# PiHat.net
KiCad netlist of a schematic drawn in EAGLE
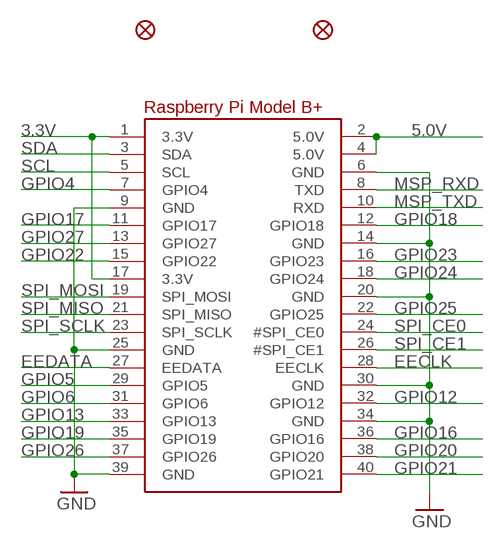
[diagram p0: schematic, sheet 1]
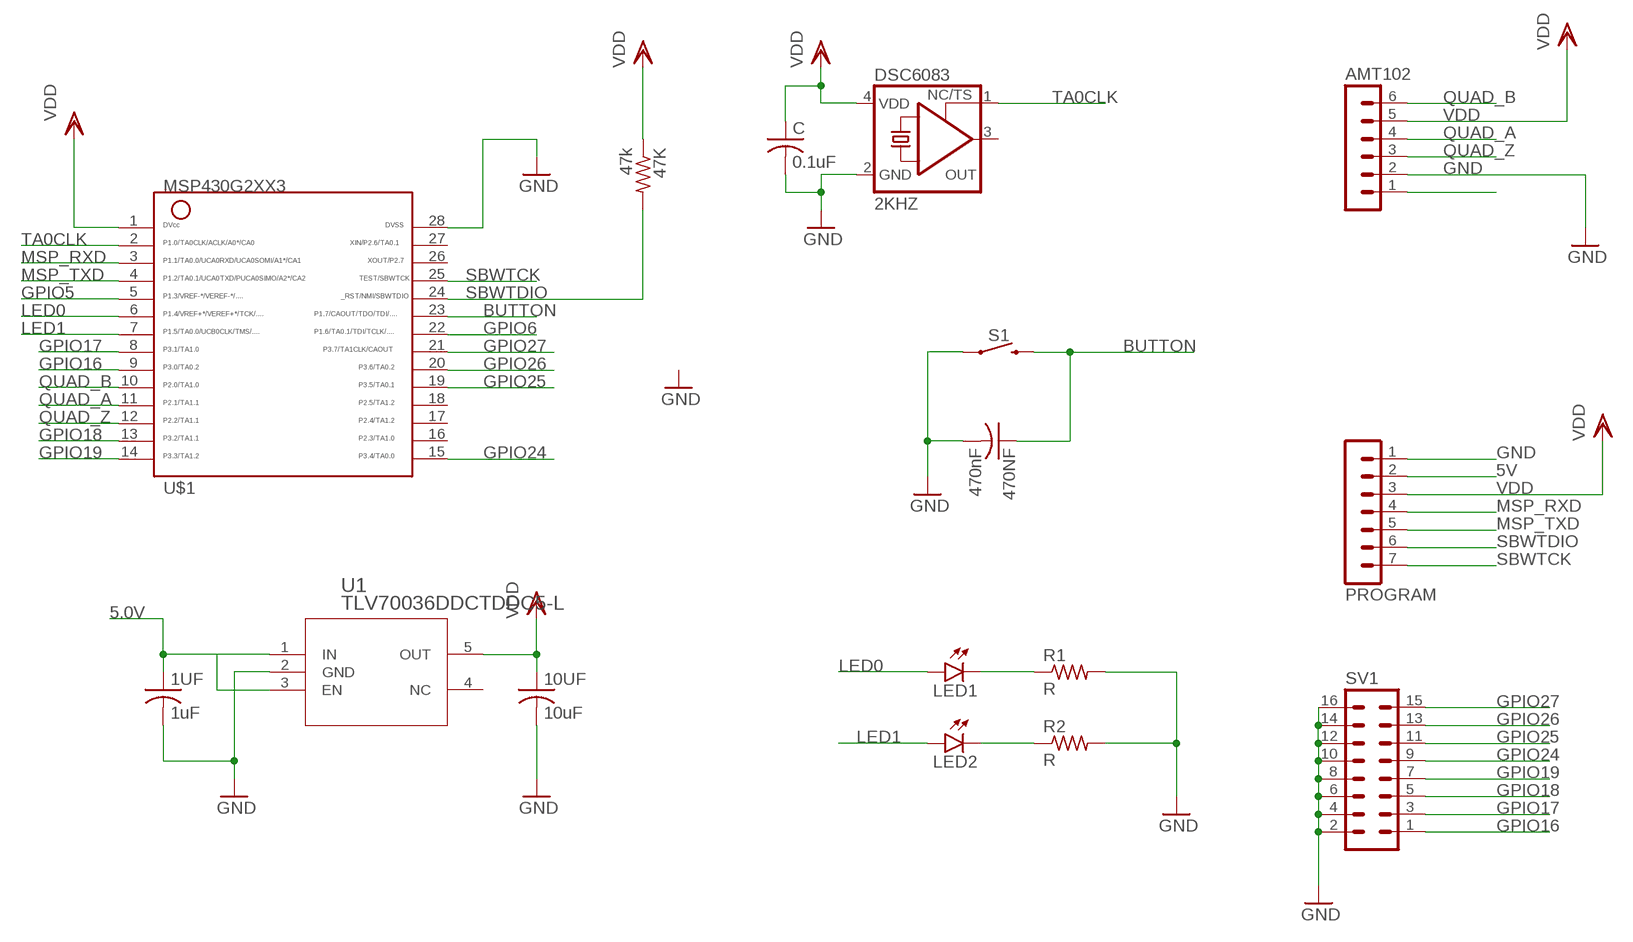
[diagram p1: schematic, sheet 2]
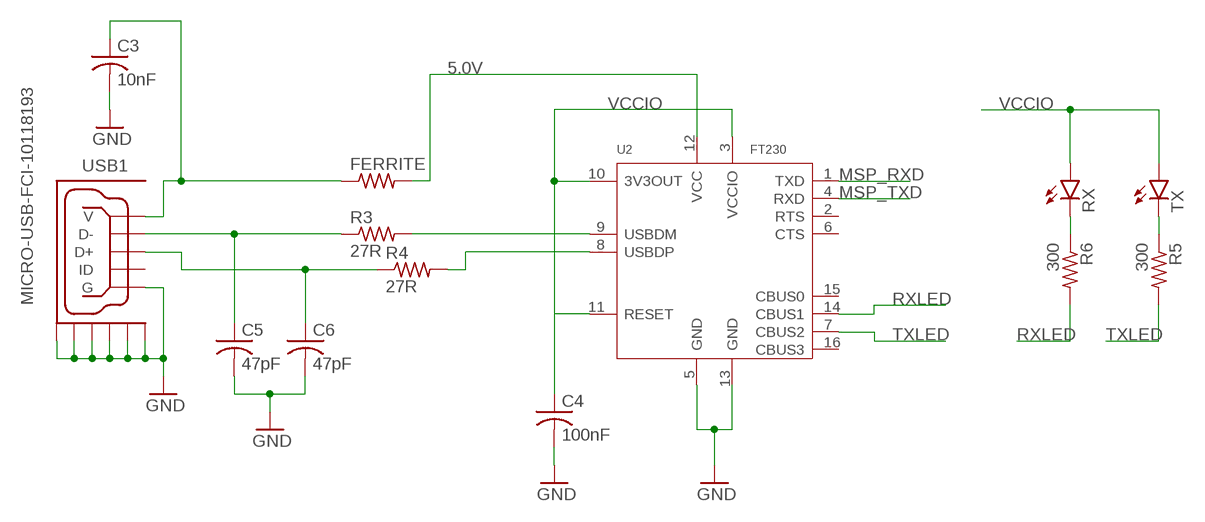
[diagram p2: schematic, sheet 3]

(export (version "E")
  (design (tool "Eeschema 10.0.6"))
  (components
    (comp (ref "FID2")
      (value "FIDUCIAL\"\"")
      (footprint "eagle-import:FIDUCIAL_1MM")
      (libsource (lib "eagle-import") (part "FIDUCIAL{dblquote}{dblquote}"))
    )
    (comp (ref "FID3")
      (value "FIDUCIAL\"\"")
      (footprint "eagle-import:FIDUCIAL_1MM")
      (libsource (lib "eagle-import") (part "FIDUCIAL{dblquote}{dblquote}"))
    )
    (comp (ref "RPI1")
      (value "RASPBERRYPI_BPLUS_HATNOSLOTS")
      (footprint "eagle-import:PI_HAT_NOSLOTS")
      (libsource (lib "eagle-import") (part "RASPBERRYPI_BPLUS_HATNOSLOTS"))
    )
    (comp (ref "C3")
      (value "10nF")
      (footprint "eagle-import:C0603")
      (libsource (lib "eagle-import") (part "resistor_348_C-USC0603"))
    )
    (comp (ref "C4")
      (value "100nF")
      (footprint "eagle-import:C0603")
      (libsource (lib "eagle-import") (part "resistor_348_C-USC0603"))
    )
    (comp (ref "C5")
      (value "47pF")
      (footprint "eagle-import:C0603")
      (libsource (lib "eagle-import") (part "resistor_348_C-USC0603"))
    )
    (comp (ref "C6")
      (value "47pF")
      (footprint "eagle-import:C0603")
      (libsource (lib "eagle-import") (part "resistor_348_C-USC0603"))
    )
    (comp (ref "FERRITE")
      (value "R-US_R0805")
      (footprint "eagle-import:R0805")
      (libsource (lib "eagle-import") (part "R-US_R0805"))
    )
    (comp (ref "R3")
      (value "27R")
      (footprint "eagle-import:R0603")
      (libsource (lib "eagle-import") (part "resistor_348_R-US_R0603"))
    )
    (comp (ref "R4")
      (value "27R")
      (footprint "eagle-import:R0603")
      (libsource (lib "eagle-import") (part "resistor_348_R-US_R0603"))
    )
    (comp (ref "R5")
      (value "300")
      (footprint "eagle-import:R0603")
      (libsource (lib "eagle-import") (part "resistor_348_R-US_R0603"))
    )
    (comp (ref "R6")
      (value "300")
      (footprint "eagle-import:R0603")
      (libsource (lib "eagle-import") (part "resistor_348_R-US_R0603"))
    )
    (comp (ref "RX")
      (value "LEDCHIPLED_1206")
      (footprint "eagle-import:CHIPLED_1206")
      (libsource (lib "eagle-import") (part "LEDCHIPLED_1206"))
    )
    (comp (ref "TX")
      (value "LEDCHIPLED_1206")
      (footprint "eagle-import:CHIPLED_1206")
      (libsource (lib "eagle-import") (part "LEDCHIPLED_1206"))
    )
    (comp (ref "U2")
      (value "FT230")
      (footprint "eagle-import:SSOP16-0.635-5X4MM")
      (fields (field (name "MPN") "FT230XS-R"))
      (libsource (lib "eagle-import") (part "INTERFACE-FT230XS-R(SSOP16)"))
    )
    (comp (ref "USB1")
      (value "MICRO-USB-FCI-10118193")
      (footprint "eagle-import:FCI-10118193-0001LF")
      (libsource (lib "eagle-import") (part "MICRO-USB-FCI-10118193"))
    )
    (comp (ref "1UF")
      (value "1uF")
      (footprint "eagle-import:C0603")
      (libsource (lib "eagle-import") (part "C-USC0603"))
    )
    (comp (ref "10UF")
      (value "10uF")
      (footprint "eagle-import:C1206")
      (libsource (lib "eagle-import") (part "C-USC1206"))
    )
    (comp (ref "47K")
      (value "47k")
      (footprint "eagle-import:R0603")
      (libsource (lib "eagle-import") (part "R-US_R0603"))
    )
    (comp (ref "470NF")
      (value "470nF")
      (footprint "eagle-import:C0603")
      (libsource (lib "eagle-import") (part "C-USC0603"))
    )
    (comp (ref "AMT102")
      (value "MA06-1")
      (footprint "eagle-import:MA06-1")
      (libsource (lib "eagle-import") (part "MA06-1"))
    )
    (comp (ref "C")
      (value "0.1uF")
      (footprint "eagle-import:C0603")
      (libsource (lib "eagle-import") (part "C-USC0603"))
    )
    (comp (ref "DSC6083")
      (value "2KHZ")
      (footprint "eagle-import:3.2X2.5_KXO-V96")
      (libsource (lib "eagle-import") (part "KXO-PXO/XO-V96"))
    )
    (comp (ref "LED1")
      (value "LEDCHIPLED_1206")
      (footprint "eagle-import:CHIPLED_1206")
      (libsource (lib "eagle-import") (part "LEDCHIPLED_1206"))
    )
    (comp (ref "LED2")
      (value "LEDCHIPLED_1206")
      (footprint "eagle-import:CHIPLED_1206")
      (libsource (lib "eagle-import") (part "LEDCHIPLED_1206"))
    )
    (comp (ref "PROGRAM")
      (value "MA07-1")
      (footprint "eagle-import:MA07-1")
      (libsource (lib "eagle-import") (part "MA07-1"))
    )
    (comp (ref "R1")
      (value "R")
      (footprint "eagle-import:R0603")
      (libsource (lib "eagle-import") (part "R-US_R0603"))
    )
    (comp (ref "R2")
      (value "R")
      (footprint "eagle-import:R0603")
      (libsource (lib "eagle-import") (part "R-US_R0603"))
    )
    (comp (ref "S1")
      (value "MOMENTARY-SWITCH-SPST-PTH-6.0MM")
      (footprint "eagle-import:TACTILE_SWITCH_PTH_6.0MM")
      (libsource (lib "eagle-import") (part "MOMENTARY-SWITCH-SPST-PTH-6.0MM"))
    )
    (comp (ref "SV1")
      (value "MA08-2")
      (footprint "eagle-import:MA08-2")
      (libsource (lib "eagle-import") (part "MA08-2"))
    )
    (comp (ref "U$1")
      (value "MSP430")
      (footprint "eagle-import:PW28")
      (libsource (lib "eagle-import") (part "G2XX3---PW28"))
    )
    (comp (ref "U1")
      (value "TLV70036DDCTDDC5-L")
      (footprint "eagle-import:DDC5-L")
      (fields (field (name "MANUFACTURER_PART_NUMBER") "TLV70036DDCT"))
      (libsource (lib "eagle-import") (part "TLV70036DDCTDDC5-L"))
    )
  )
  (nets
    (net (code "1") (name "3.3V") (class "Default")
      (node (ref "RPI1") (pin "1") (pinfunction "3.3V_1") (pintype "power_in"))
      (node (ref "RPI1") (pin "17") (pinfunction "3.3V_17") (pintype "power_in"))
    )
    (net (code "2") (name "5.0V") (class "Default")
      (node (ref "1UF") (pin "1") (pinfunction "1_1") (pintype "passive"))
      (node (ref "FERRITE") (pin "2") (pinfunction "2_2") (pintype "passive"))
      (node (ref "RPI1") (pin "2") (pinfunction "5.0V_2") (pintype "power_in"))
      (node (ref "RPI1") (pin "4") (pinfunction "5.0V_4") (pintype "power_in"))
      (node (ref "U1") (pin "1") (pinfunction "IN_1") (pintype "input"))
      (node (ref "U1") (pin "3") (pinfunction "EN_3") (pintype "passive"))
      (node (ref "U2") (pin "12") (pinfunction "VCC_12") (pintype "bidirectional"))
    )
    (net (code "3") (name "5V") (class "Default")
      (node (ref "PROGRAM") (pin "2") (pinfunction "2_2") (pintype "passive"))
    )
    (net (code "4") (name "BUTTON") (class "Default")
      (node (ref "470NF") (pin "1") (pinfunction "1_1") (pintype "passive"))
      (node (ref "S1") (pin "3") (pinfunction "2_3") (pintype "passive"))
      (node (ref "U$1") (pin "23") (pinfunction "23_23") (pintype "bidirectional"))
    )
    (net (code "5") (name "EECLK") (class "Default")
      (node (ref "RPI1") (pin "28") (pinfunction "EECLK_28") (pintype "power_in"))
    )
    (net (code "6") (name "EEDATA") (class "Default")
      (node (ref "RPI1") (pin "27") (pinfunction "EEDATA_27") (pintype "bidirectional"))
    )
    (net (code "7") (name "GND") (class "Default")
      (node (ref "10UF") (pin "2") (pinfunction "2_2") (pintype "passive"))
      (node (ref "1UF") (pin "2") (pinfunction "2_2") (pintype "passive"))
      (node (ref "470NF") (pin "2") (pinfunction "2_2") (pintype "passive"))
      (node (ref "AMT102") (pin "2") (pinfunction "2_2") (pintype "passive"))
      (node (ref "C") (pin "2") (pinfunction "2_2") (pintype "passive"))
      (node (ref "C3") (pin "2") (pinfunction "2_2") (pintype "passive"))
      (node (ref "C4") (pin "2") (pinfunction "2_2") (pintype "passive"))
      (node (ref "C5") (pin "2") (pinfunction "2_2") (pintype "passive"))
      (node (ref "C6") (pin "2") (pinfunction "2_2") (pintype "passive"))
      (node (ref "DSC6083") (pin "2") (pinfunction "GND_2") (pintype "power_in"))
      (node (ref "PROGRAM") (pin "1") (pinfunction "1_1") (pintype "passive"))
      (node (ref "R1") (pin "2") (pinfunction "2_2") (pintype "passive"))
      (node (ref "R2") (pin "2") (pinfunction "2_2") (pintype "passive"))
      (node (ref "RPI1") (pin "14") (pinfunction "GND_14") (pintype "power_in"))
      (node (ref "RPI1") (pin "20") (pinfunction "GND_20") (pintype "power_in"))
      (node (ref "RPI1") (pin "25") (pinfunction "GND_25") (pintype "power_in"))
      (node (ref "RPI1") (pin "30") (pinfunction "GND_30") (pintype "bidirectional"))
      (node (ref "RPI1") (pin "34") (pinfunction "GND_34") (pintype "bidirectional"))
      (node (ref "RPI1") (pin "39") (pinfunction "GND_39") (pintype "power_in"))
      (node (ref "RPI1") (pin "6") (pinfunction "GND_6") (pintype "power_in"))
      (node (ref "RPI1") (pin "9") (pinfunction "GND_9") (pintype "power_in"))
      (node (ref "S1") (pin "1") (pinfunction "1_1") (pintype "passive"))
      (node (ref "SV1") (pin "10") (pinfunction "10_10") (pintype "passive"))
      (node (ref "SV1") (pin "12") (pinfunction "12_12") (pintype "passive"))
      (node (ref "SV1") (pin "14") (pinfunction "14_14") (pintype "passive"))
      (node (ref "SV1") (pin "16") (pinfunction "16_16") (pintype "passive"))
      (node (ref "SV1") (pin "2") (pinfunction "2_2") (pintype "passive"))
      (node (ref "SV1") (pin "4") (pinfunction "4_4") (pintype "passive"))
      (node (ref "SV1") (pin "6") (pinfunction "6_6") (pintype "passive"))
      (node (ref "SV1") (pin "8") (pinfunction "8_8") (pintype "passive"))
      (node (ref "U$1") (pin "28") (pinfunction "28_28") (pintype "bidirectional"))
      (node (ref "U1") (pin "2") (pinfunction "GND_2") (pintype "power_in"))
      (node (ref "U2") (pin "13") (pinfunction "GND_13") (pintype "bidirectional"))
      (node (ref "U2") (pin "5") (pinfunction "GND_5") (pintype "bidirectional"))
      (node (ref "USB1") (pin "5") (pinfunction "G_5") (pintype "input"))
      (node (ref "USB1") (pin "G1") (pinfunction "GND1_G1") (pintype "power_in"))
      (node (ref "USB1") (pin "G2") (pinfunction "GND2_G2") (pintype "power_in"))
      (node (ref "USB1") (pin "G3") (pinfunction "GND3_G3") (pintype "power_in"))
      (node (ref "USB1") (pin "G4") (pinfunction "GND4_G4") (pintype "power_in"))
      (node (ref "USB1") (pin "G5") (pinfunction "GND5_G5") (pintype "power_in"))
      (node (ref "USB1") (pin "G6") (pinfunction "GND6_G6") (pintype "power_in"))
    )
    (net (code "8") (name "GPIO4") (class "Default")
      (node (ref "RPI1") (pin "7") (pinfunction "GPIO4_7") (pintype "bidirectional"))
    )
    (net (code "9") (name "GPIO5") (class "Default")
      (node (ref "RPI1") (pin "29") (pinfunction "GPIO5_29") (pintype "bidirectional"))
      (node (ref "U$1") (pin "5") (pinfunction "5_5") (pintype "bidirectional"))
    )
    (net (code "10") (name "GPIO6") (class "Default")
      (node (ref "RPI1") (pin "31") (pinfunction "GPIO6_31") (pintype "power_in"))
      (node (ref "U$1") (pin "22") (pinfunction "22_22") (pintype "bidirectional"))
    )
    (net (code "11") (name "GPIO12") (class "Default")
      (node (ref "RPI1") (pin "32") (pinfunction "GPIO12_32") (pintype "bidirectional"))
    )
    (net (code "12") (name "GPIO13") (class "Default")
      (node (ref "RPI1") (pin "33") (pinfunction "GPIO13_33") (pintype "bidirectional"))
    )
    (net (code "13") (name "GPIO16") (class "Default")
      (node (ref "RPI1") (pin "36") (pinfunction "GPIO16_36") (pintype "power_in"))
      (node (ref "SV1") (pin "1") (pinfunction "1_1") (pintype "passive"))
      (node (ref "U$1") (pin "9") (pinfunction "9_9") (pintype "bidirectional"))
    )
    (net (code "14") (name "GPIO17") (class "Default")
      (node (ref "RPI1") (pin "11") (pinfunction "GPIO17_11") (pintype "bidirectional"))
      (node (ref "SV1") (pin "3") (pinfunction "3_3") (pintype "passive"))
      (node (ref "U$1") (pin "8") (pinfunction "8_8") (pintype "bidirectional"))
    )
    (net (code "15") (name "GPIO18") (class "Default")
      (node (ref "RPI1") (pin "12") (pinfunction "GPIO18_12") (pintype "bidirectional"))
      (node (ref "SV1") (pin "5") (pinfunction "5_5") (pintype "passive"))
      (node (ref "U$1") (pin "13") (pinfunction "13_13") (pintype "bidirectional"))
    )
    (net (code "16") (name "GPIO19") (class "Default")
      (node (ref "RPI1") (pin "35") (pinfunction "GPIO19_35") (pintype "bidirectional"))
      (node (ref "SV1") (pin "7") (pinfunction "7_7") (pintype "passive"))
      (node (ref "U$1") (pin "14") (pinfunction "14_14") (pintype "bidirectional"))
    )
    (net (code "17") (name "GPIO20") (class "Default")
      (node (ref "RPI1") (pin "38") (pinfunction "GPIO20_38") (pintype "bidirectional"))
    )
    (net (code "18") (name "GPIO21") (class "Default")
      (node (ref "RPI1") (pin "40") (pinfunction "GPIO21_40") (pintype "bidirectional"))
    )
    (net (code "19") (name "GPIO22") (class "Default")
      (node (ref "RPI1") (pin "15") (pinfunction "GPIO22_15") (pintype "bidirectional"))
    )
    (net (code "20") (name "GPIO23") (class "Default")
      (node (ref "RPI1") (pin "16") (pinfunction "GPIO23_16") (pintype "bidirectional"))
    )
    (net (code "21") (name "GPIO24") (class "Default")
      (node (ref "RPI1") (pin "18") (pinfunction "GPIO24_18") (pintype "bidirectional"))
      (node (ref "SV1") (pin "9") (pinfunction "9_9") (pintype "passive"))
      (node (ref "U$1") (pin "15") (pinfunction "15_15") (pintype "bidirectional"))
    )
    (net (code "22") (name "GPIO25") (class "Default")
      (node (ref "RPI1") (pin "22") (pinfunction "GPIO25_22") (pintype "bidirectional"))
      (node (ref "SV1") (pin "11") (pinfunction "11_11") (pintype "passive"))
      (node (ref "U$1") (pin "19") (pinfunction "19_19") (pintype "bidirectional"))
    )
    (net (code "23") (name "GPIO26") (class "Default")
      (node (ref "RPI1") (pin "37") (pinfunction "GPIO26_37") (pintype "bidirectional"))
      (node (ref "SV1") (pin "13") (pinfunction "13_13") (pintype "passive"))
      (node (ref "U$1") (pin "20") (pinfunction "20_20") (pintype "bidirectional"))
    )
    (net (code "24") (name "GPIO27") (class "Default")
      (node (ref "RPI1") (pin "13") (pinfunction "GPIO27_13") (pintype "bidirectional"))
      (node (ref "SV1") (pin "15") (pinfunction "15_15") (pintype "passive"))
      (node (ref "U$1") (pin "21") (pinfunction "21_21") (pintype "bidirectional"))
    )
    (net (code "25") (name "LED0") (class "Default")
      (node (ref "LED1") (pin "A") (pinfunction "A_A") (pintype "passive"))
      (node (ref "U$1") (pin "6") (pinfunction "6_6") (pintype "bidirectional"))
    )
    (net (code "26") (name "LED1") (class "Default")
      (node (ref "LED2") (pin "A") (pinfunction "A_A") (pintype "passive"))
      (node (ref "U$1") (pin "7") (pinfunction "7_7") (pintype "bidirectional"))
    )
    (net (code "27") (name "MSP_RXD") (class "Default")
      (node (ref "PROGRAM") (pin "4") (pinfunction "4_4") (pintype "passive"))
      (node (ref "RPI1") (pin "8") (pinfunction "TXD_8") (pintype "output"))
      (node (ref "U$1") (pin "3") (pinfunction "3_3") (pintype "bidirectional"))
      (node (ref "U2") (pin "1") (pinfunction "TXD_1") (pintype "bidirectional"))
    )
    (net (code "28") (name "MSP_TXD") (class "Default")
      (node (ref "PROGRAM") (pin "5") (pinfunction "5_5") (pintype "passive"))
      (node (ref "RPI1") (pin "10") (pinfunction "RXD_10") (pintype "bidirectional"))
      (node (ref "U$1") (pin "4") (pinfunction "4_4") (pintype "bidirectional"))
      (node (ref "U2") (pin "4") (pinfunction "RXD_4") (pintype "bidirectional"))
    )
    (net (code "29") (name "Net-(LED1-PadC)") (class "Default")
      (node (ref "LED1") (pin "C") (pinfunction "C_C") (pintype "passive"))
      (node (ref "R1") (pin "1") (pinfunction "1_1") (pintype "passive"))
    )
    (net (code "30") (name "Net-(LED2-PadC)") (class "Default")
      (node (ref "LED2") (pin "C") (pinfunction "C_C") (pintype "passive"))
      (node (ref "R2") (pin "1") (pinfunction "1_1") (pintype "passive"))
    )
    (net (code "31") (name "Net-(R5-Pad1)") (class "Default")
      (node (ref "R5") (pin "1") (pinfunction "1_1") (pintype "passive"))
      (node (ref "TX") (pin "C") (pinfunction "C_C") (pintype "passive"))
    )
    (net (code "32") (name "Net-(R6-Pad1)") (class "Default")
      (node (ref "R6") (pin "1") (pinfunction "1_1") (pintype "passive"))
      (node (ref "RX") (pin "C") (pinfunction "C_C") (pintype "passive"))
    )
    (net (code "33") (name "Net-(U2-USBDM)") (class "Default")
      (node (ref "R3") (pin "2") (pinfunction "2_2") (pintype "passive"))
      (node (ref "U2") (pin "9") (pinfunction "USBDM_9") (pintype "bidirectional"))
    )
    (net (code "34") (name "Net-(U2-USBDP)") (class "Default")
      (node (ref "R4") (pin "2") (pinfunction "2_2") (pintype "passive"))
      (node (ref "U2") (pin "8") (pinfunction "USBDP_8") (pintype "bidirectional"))
    )
    (net (code "35") (name "Net-(USB1-D+)") (class "Default")
      (node (ref "C6") (pin "1") (pinfunction "1_1") (pintype "passive"))
      (node (ref "R4") (pin "1") (pinfunction "1_1") (pintype "passive"))
      (node (ref "USB1") (pin "3") (pinfunction "D+_3") (pintype "input"))
    )
    (net (code "36") (name "Net-(USB1-D-)") (class "Default")
      (node (ref "C5") (pin "1") (pinfunction "1_1") (pintype "passive"))
      (node (ref "R3") (pin "1") (pinfunction "1_1") (pintype "passive"))
      (node (ref "USB1") (pin "2") (pinfunction "D-_2") (pintype "input"))
    )
    (net (code "37") (name "Net-(USB1-V)") (class "Default")
      (node (ref "C3") (pin "1") (pinfunction "1_1") (pintype "passive"))
      (node (ref "FERRITE") (pin "1") (pinfunction "1_1") (pintype "passive"))
      (node (ref "USB1") (pin "1") (pinfunction "V_1") (pintype "input"))
    )
    (net (code "38") (name "QUAD_A") (class "Default")
      (node (ref "AMT102") (pin "4") (pinfunction "4_4") (pintype "passive"))
      (node (ref "U$1") (pin "11") (pinfunction "11_11") (pintype "bidirectional"))
    )
    (net (code "39") (name "QUAD_B") (class "Default")
      (node (ref "AMT102") (pin "6") (pinfunction "6_6") (pintype "passive"))
      (node (ref "U$1") (pin "10") (pinfunction "10_10") (pintype "bidirectional"))
    )
    (net (code "40") (name "QUAD_Z") (class "Default")
      (node (ref "AMT102") (pin "3") (pinfunction "3_3") (pintype "passive"))
      (node (ref "U$1") (pin "12") (pinfunction "12_12") (pintype "bidirectional"))
    )
    (net (code "41") (name "RXLED") (class "Default")
      (node (ref "R6") (pin "2") (pinfunction "2_2") (pintype "passive"))
      (node (ref "U2") (pin "14") (pinfunction "CBUS1_14") (pintype "bidirectional"))
    )
    (net (code "42") (name "SBWTCK") (class "Default")
      (node (ref "PROGRAM") (pin "7") (pinfunction "7_7") (pintype "passive"))
      (node (ref "U$1") (pin "25") (pinfunction "25_25") (pintype "bidirectional"))
    )
    (net (code "43") (name "SBWTDIO") (class "Default")
      (node (ref "47K") (pin "2") (pinfunction "2_2") (pintype "passive"))
      (node (ref "PROGRAM") (pin "6") (pinfunction "6_6") (pintype "passive"))
      (node (ref "U$1") (pin "24") (pinfunction "24_24") (pintype "bidirectional"))
    )
    (net (code "44") (name "SCL") (class "Default")
      (node (ref "RPI1") (pin "5") (pinfunction "SCL_5") (pintype "bidirectional"))
    )
    (net (code "45") (name "SDA") (class "Default")
      (node (ref "RPI1") (pin "3") (pinfunction "SDA_3") (pintype "bidirectional"))
    )
    (net (code "46") (name "SPI_CE0") (class "Default")
      (node (ref "RPI1") (pin "24") (pinfunction "#SPI_CE0_24") (pintype "bidirectional"))
    )
    (net (code "47") (name "SPI_CE1") (class "Default")
      (node (ref "RPI1") (pin "26") (pinfunction "#SPI_CE1_26") (pintype "bidirectional"))
    )
    (net (code "48") (name "SPI_MISO") (class "Default")
      (node (ref "RPI1") (pin "21") (pinfunction "SPI_MISO_21") (pintype "bidirectional"))
    )
    (net (code "49") (name "SPI_MOSI") (class "Default")
      (node (ref "RPI1") (pin "19") (pinfunction "SPI_MOSI_19") (pintype "bidirectional"))
    )
    (net (code "50") (name "SPI_SCLK") (class "Default")
      (node (ref "RPI1") (pin "23") (pinfunction "SPI_SCLK_23") (pintype "bidirectional"))
    )
    (net (code "51") (name "TA0CLK") (class "Default")
      (node (ref "DSC6083") (pin "1") (pinfunction "TS_1") (pintype "passive"))
      (node (ref "U$1") (pin "2") (pinfunction "2_2") (pintype "bidirectional"))
    )
    (net (code "52") (name "TXLED") (class "Default")
      (node (ref "R5") (pin "2") (pinfunction "2_2") (pintype "passive"))
      (node (ref "U2") (pin "7") (pinfunction "CBUS2_7") (pintype "bidirectional"))
    )
    (net (code "53") (name "VCCIO") (class "Default")
      (node (ref "C4") (pin "1") (pinfunction "1_1") (pintype "passive"))
      (node (ref "RX") (pin "A") (pinfunction "A_A") (pintype "passive"))
      (node (ref "TX") (pin "A") (pinfunction "A_A") (pintype "passive"))
      (node (ref "U2") (pin "10") (pinfunction "3V3OUT_10") (pintype "bidirectional"))
      (node (ref "U2") (pin "11") (pinfunction "RESET_11") (pintype "bidirectional"))
      (node (ref "U2") (pin "3") (pinfunction "VCCIO_3") (pintype "bidirectional"))
    )
    (net (code "54") (name "VDD") (class "Default")
      (node (ref "10UF") (pin "1") (pinfunction "1_1") (pintype "passive"))
      (node (ref "47K") (pin "1") (pinfunction "1_1") (pintype "passive"))
      (node (ref "AMT102") (pin "5") (pinfunction "5_5") (pintype "passive"))
      (node (ref "C") (pin "1") (pinfunction "1_1") (pintype "passive"))
      (node (ref "DSC6083") (pin "4") (pinfunction "VDD_4") (pintype "power_in"))
      (node (ref "PROGRAM") (pin "3") (pinfunction "3_3") (pintype "passive"))
      (node (ref "U$1") (pin "1") (pinfunction "1_1") (pintype "bidirectional"))
      (node (ref "U1") (pin "5") (pinfunction "OUT_5") (pintype "output"))
    )
    (net (code "55") (name "unconnected-(AMT102-Pad1)") (class "Default")
      (node (ref "AMT102") (pin "1") (pinfunction "1_1") (pintype "passive"))
    )
    (net (code "56") (name "unconnected-(DSC6083-OUT-Pad3)") (class "Default")
      (node (ref "DSC6083") (pin "3") (pinfunction "OUT_3") (pintype "output"))
    )
    (net (code "57") (name "unconnected-(U$1-Pad16)") (class "Default")
      (node (ref "U$1") (pin "16") (pinfunction "16_16") (pintype "bidirectional"))
    )
    (net (code "58") (name "unconnected-(U$1-Pad17)") (class "Default")
      (node (ref "U$1") (pin "17") (pinfunction "17_17") (pintype "bidirectional"))
    )
    (net (code "59") (name "unconnected-(U$1-Pad18)") (class "Default")
      (node (ref "U$1") (pin "18") (pinfunction "18_18") (pintype "bidirectional"))
    )
    (net (code "60") (name "unconnected-(U$1-Pad26)") (class "Default")
      (node (ref "U$1") (pin "26") (pinfunction "26_26") (pintype "bidirectional"))
    )
    (net (code "61") (name "unconnected-(U$1-Pad27)") (class "Default")
      (node (ref "U$1") (pin "27") (pinfunction "27_27") (pintype "bidirectional"))
    )
    (net (code "62") (name "unconnected-(U1-NC-Pad4)") (class "Default")
      (node (ref "U1") (pin "4") (pinfunction "NC_4") (pintype "passive"))
    )
    (net (code "63") (name "unconnected-(U2-CBUS0-Pad15)") (class "Default")
      (node (ref "U2") (pin "15") (pinfunction "CBUS0_15") (pintype "bidirectional"))
    )
    (net (code "64") (name "unconnected-(U2-CBUS3-Pad16)") (class "Default")
      (node (ref "U2") (pin "16") (pinfunction "CBUS3_16") (pintype "bidirectional"))
    )
    (net (code "65") (name "unconnected-(U2-CTS-Pad6)") (class "Default")
      (node (ref "U2") (pin "6") (pinfunction "CTS_6") (pintype "bidirectional"))
    )
    (net (code "66") (name "unconnected-(U2-RTS-Pad2)") (class "Default")
      (node (ref "U2") (pin "2") (pinfunction "RTS_2") (pintype "bidirectional"))
    )
    (net (code "67") (name "unconnected-(USB1-ID-Pad4)") (class "Default")
      (node (ref "USB1") (pin "4") (pinfunction "ID_4") (pintype "input"))
    )
  )
)
